# design.net
KiCad netlist of a schematic drawn in EasyEDA Pro
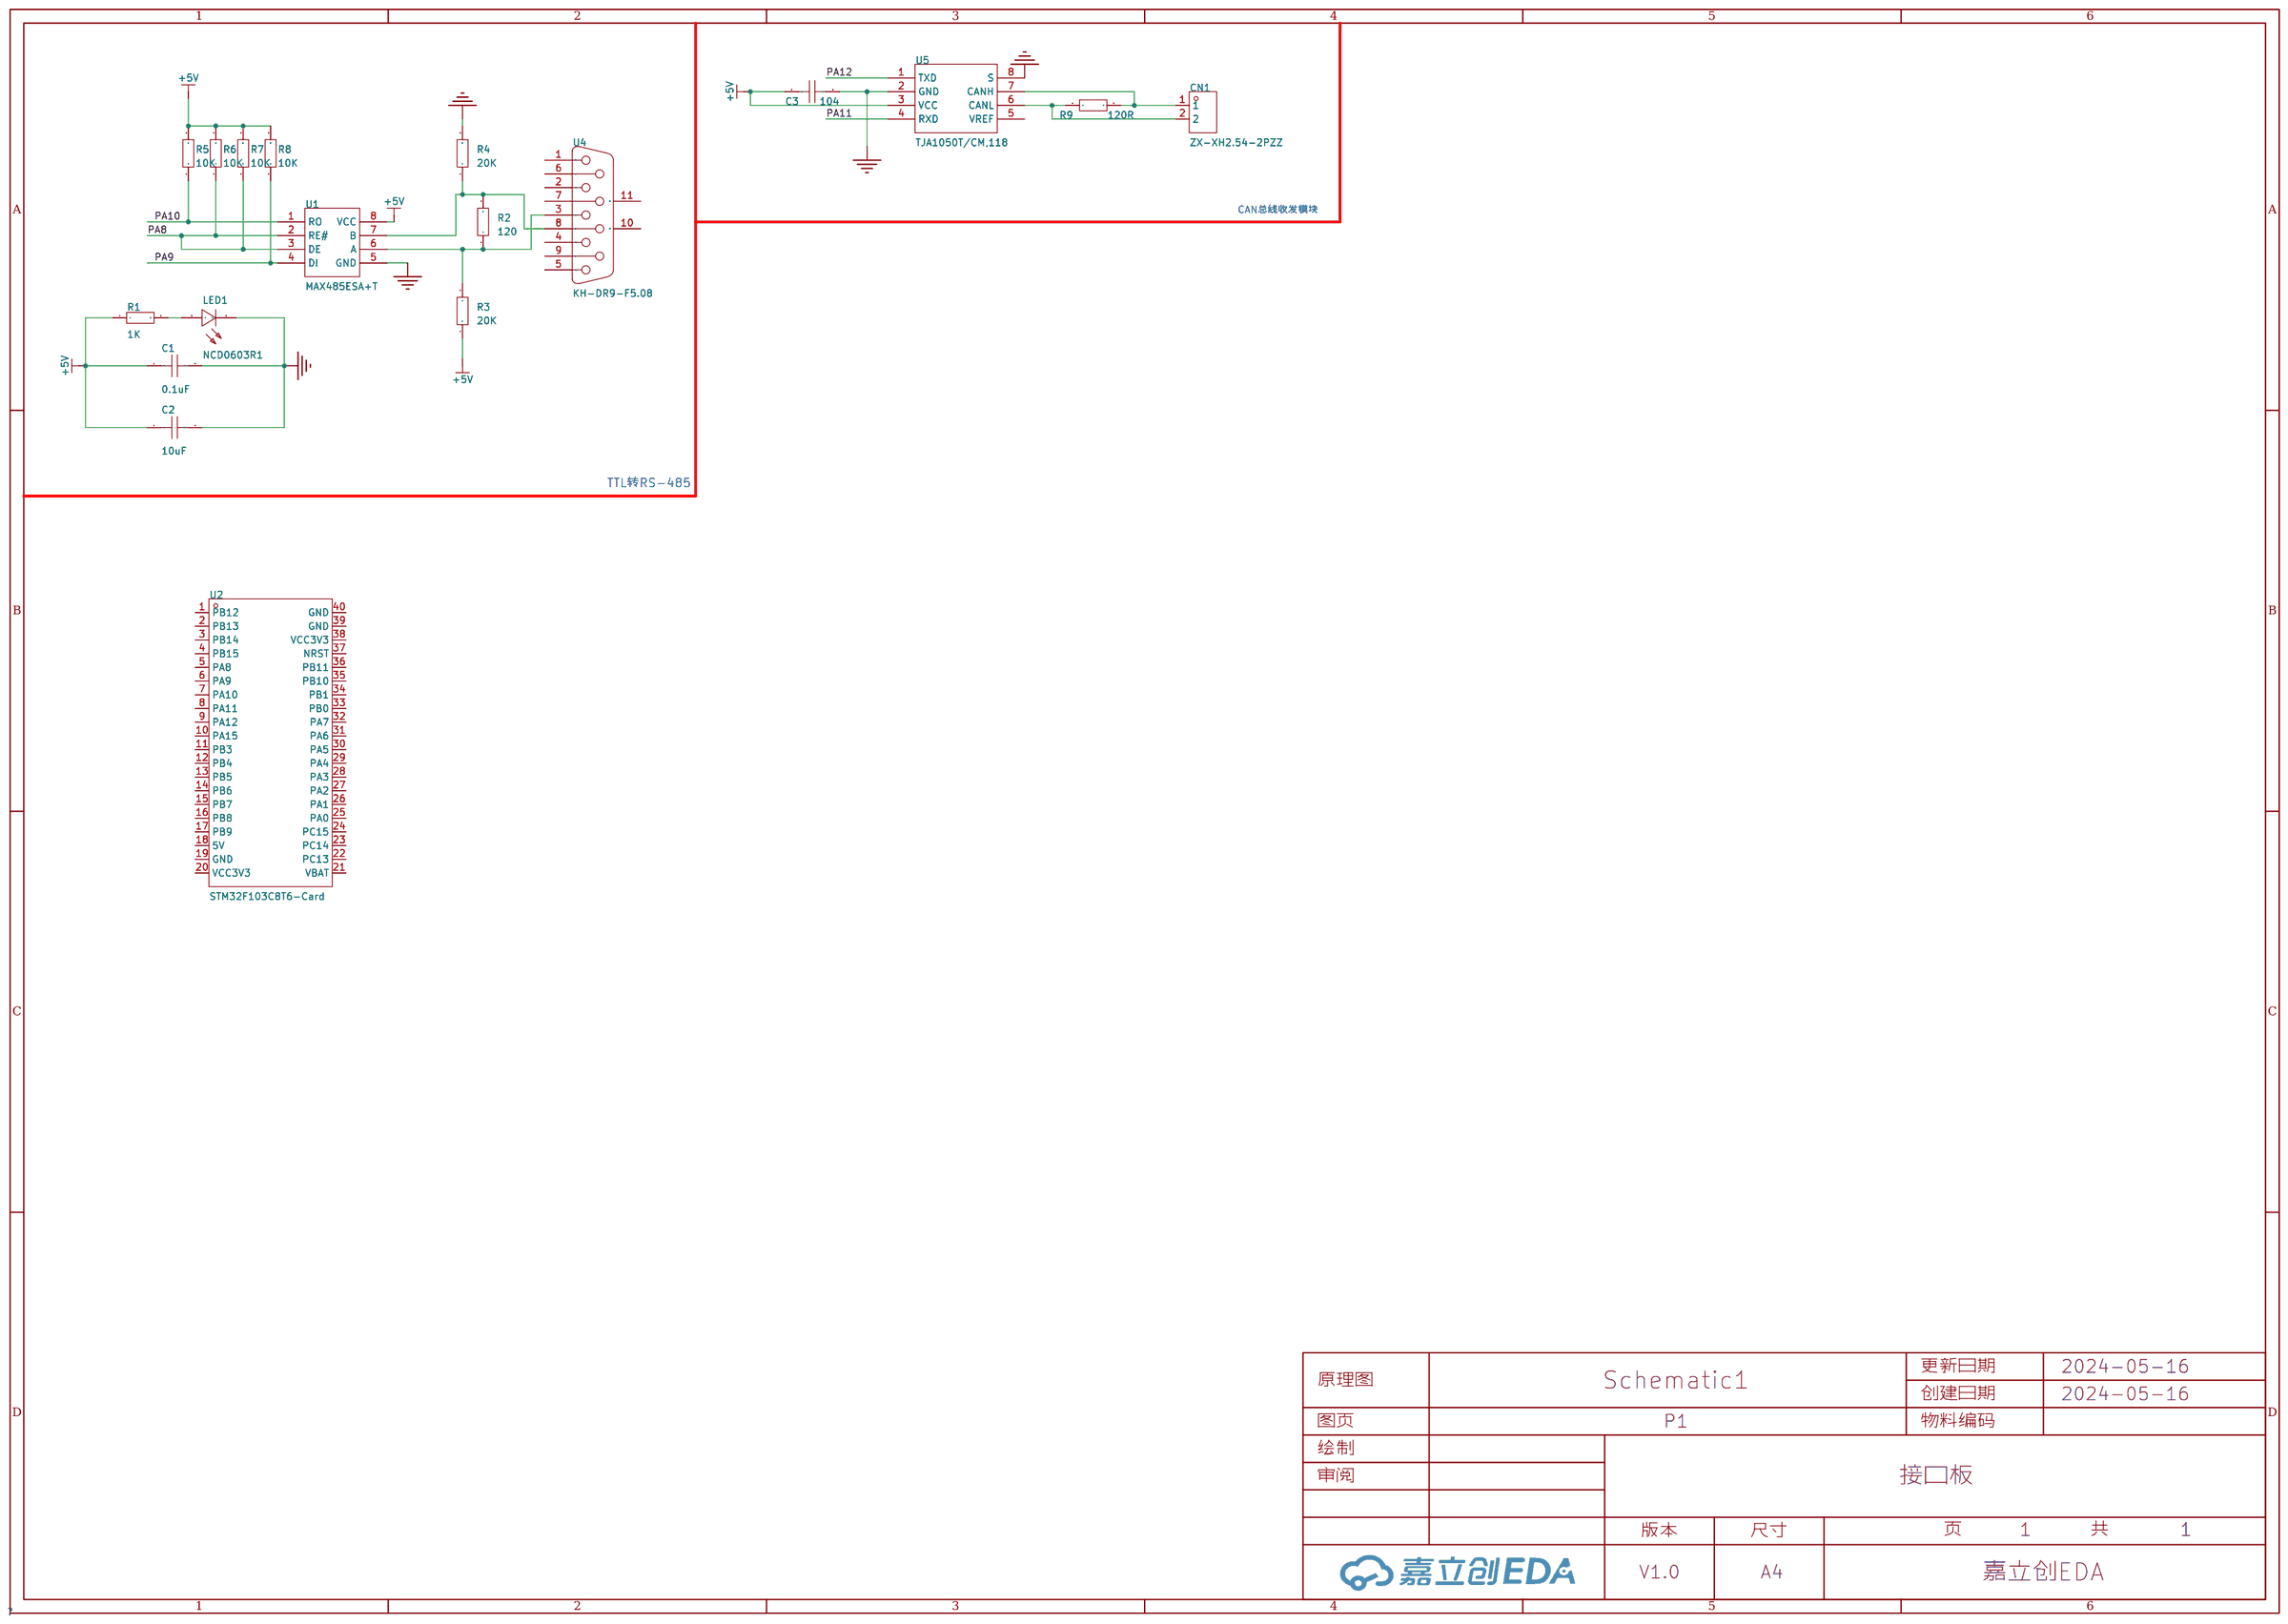
[diagram p0: schematic sheet]

(export (version "E")
  (design (tool "Eeschema 10.0.6"))
  (components
    (comp (ref "C1")
      (value "0.1uF")
      (footprint "easyedapro:C0603")
      (libsource (lib "easyedapro") (part "CapAcitance"))
    )
    (comp (ref "C2")
      (value "10uF")
      (footprint "easyedapro:C0603")
      (libsource (lib "easyedapro") (part "CapAcitance"))
    )
    (comp (ref "C3")
      (value "104")
      (footprint "easyedapro:C0603")
      (libsource (lib "easyedapro") (part "CapAcitance"))
    )
    (comp (ref "CN1")
      (value "ZX-XH2.54-2PZZ")
      (footprint "easyedapro:CONN-TH_2P-P2.50_HX25003-2A")
      (fields (field (name "Manufacturer") "Megastar(兆星)"))
      (libsource (lib "easyedapro") (part "ZX-XH2.54-2PZZ"))
    )
    (comp (ref "LED1")
      (value "NCD0603R1")
      (footprint "easyedapro:LED0603-RD_RED")
      (fields (field (name "Manufacturer") "国星光电"))
      (libsource (lib "easyedapro") (part "FC-DA1608HRK-620D"))
    )
    (comp (ref "R1") (value "1K") (footprint "easyedapro:R0603") (libsource (lib "easyedapro") (part "电阻")))
    (comp (ref "R2") (value "120") (footprint "easyedapro:R0603") (libsource (lib "easyedapro") (part "电阻")))
    (comp (ref "R3") (value "20K") (footprint "easyedapro:R0603") (libsource (lib "easyedapro") (part "电阻")))
    (comp (ref "R4") (value "20K") (footprint "easyedapro:R0603") (libsource (lib "easyedapro") (part "电阻")))
    (comp (ref "R5") (value "10K") (footprint "easyedapro:R0603") (libsource (lib "easyedapro") (part "电阻")))
    (comp (ref "R6") (value "10K") (footprint "easyedapro:R0603") (libsource (lib "easyedapro") (part "电阻")))
    (comp (ref "R7") (value "10K") (footprint "easyedapro:R0603") (libsource (lib "easyedapro") (part "电阻")))
    (comp (ref "R8") (value "10K") (footprint "easyedapro:R0603") (libsource (lib "easyedapro") (part "电阻")))
    (comp (ref "R9") (value "120R") (footprint "easyedapro:R0603") (libsource (lib "easyedapro") (part "电阻")))
    (comp (ref "U1")
      (value "MAX485ESA+T")
      (footprint "easyedapro:SOIC-8_L5.0-W4.0-P1.27-LS6.0-BL")
      (description "类型:收发器;数据速率:2.5Mbps;驱动器/接收器:1/1;")
      (fields (field (name "Manufacturer") "ADI(亚德诺)/MAXIM(美信)"))
      (libsource (lib "easyedapro") (part "MAX485ESA+T"))
    )
    (comp (ref "U2")
      (value "STM32F103C8T6-Card")
      (footprint "easyedapro:CONN-TH_L53.3-W22.9_STM32F103C8T6-CARD")
      (libsource (lib "easyedapro") (part "STM32F103C8T6-CARD"))
    )
    (comp (ref "U4")
      (value "KH-DR9-F5.08")
      (footprint "easyedapro:DB9-TH_KH-DR9-F5.08")
      (description "连接器类型:D-Sub;公母:母;总PIN位数:9P;")
      (fields (field (name "Manufacturer") "kinghelm(金航标)"))
      (libsource (lib "easyedapro") (part "KH-DR9-F5.08"))
    )
    (comp (ref "U5")
      (value "TJA1050T/CM,118")
      (footprint "easyedapro:SOIC-8_L5.0-W4.0-P1.27-LS6.0-BL")
      (description "类型:收发器;")
      (fields (field (name "Manufacturer") "NXP(恩智浦)"))
      (libsource (lib "easyedapro") (part "TJA1050T/CM,118"))
    )
  )
  (nets
    (net (code "1") (name "+5V") (class "Default")
      (node (ref "C1") (pin "1") (pinfunction "1_1") (pintype "input"))
      (node (ref "C2") (pin "1") (pinfunction "1_1") (pintype "input"))
      (node (ref "C3") (pin "1") (pinfunction "1_1") (pintype "input"))
      (node (ref "R1") (pin "1") (pinfunction "1_1") (pintype "input"))
      (node (ref "R3") (pin "1") (pinfunction "1_1") (pintype "input"))
      (node (ref "R5") (pin "2") (pinfunction "2_2") (pintype "input"))
      (node (ref "R6") (pin "2") (pinfunction "2_2") (pintype "input"))
      (node (ref "R7") (pin "2") (pinfunction "2_2") (pintype "input"))
      (node (ref "R8") (pin "2") (pinfunction "2_2") (pintype "input"))
      (node (ref "U1") (pin "8") (pinfunction "VCC_8") (pintype "unspecified"))
      (node (ref "U5") (pin "3") (pinfunction "VCC_3") (pintype "unspecified"))
    )
    (net (code "2") (name "/PA8") (class "Default")
      (node (ref "R6") (pin "1") (pinfunction "1_1") (pintype "input"))
      (node (ref "R7") (pin "1") (pinfunction "1_1") (pintype "input"))
      (node (ref "U1") (pin "2") (pinfunction "RE#_2") (pintype "unspecified"))
      (node (ref "U1") (pin "3") (pinfunction "DE_3") (pintype "unspecified"))
    )
    (net (code "3") (name "/PA9") (class "Default")
      (node (ref "R8") (pin "1") (pinfunction "1_1") (pintype "input"))
      (node (ref "U1") (pin "4") (pinfunction "DI_4") (pintype "unspecified"))
    )
    (net (code "4") (name "/PA10") (class "Default")
      (node (ref "R5") (pin "1") (pinfunction "1_1") (pintype "input"))
      (node (ref "U1") (pin "1") (pinfunction "RO_1") (pintype "unspecified"))
    )
    (net (code "5") (name "/PA11") (class "Default")
      (node (ref "U5") (pin "4") (pinfunction "RXD_4") (pintype "unspecified"))
    )
    (net (code "6") (name "/PA12") (class "Default")
      (node (ref "U5") (pin "1") (pinfunction "TXD_1") (pintype "unspecified"))
    )
    (net (code "7") (name "GND") (class "Default")
      (node (ref "C1") (pin "2") (pinfunction "2_2") (pintype "input"))
      (node (ref "C2") (pin "2") (pinfunction "2_2") (pintype "input"))
      (node (ref "C3") (pin "2") (pinfunction "2_2") (pintype "input"))
      (node (ref "LED1") (pin "1") (pinfunction "K_1") (pintype "input"))
      (node (ref "R4") (pin "2") (pinfunction "2_2") (pintype "input"))
      (node (ref "U1") (pin "5") (pinfunction "GND_5") (pintype "unspecified"))
      (node (ref "U5") (pin "2") (pinfunction "GND_2") (pintype "unspecified"))
      (node (ref "U5") (pin "8") (pinfunction "S_8") (pintype "unspecified"))
    )
    (net (code "8") (name "Net-(LED1-A)") (class "Default")
      (node (ref "LED1") (pin "2") (pinfunction "A_2") (pintype "input"))
      (node (ref "R1") (pin "2") (pinfunction "2_2") (pintype "input"))
    )
    (net (code "9") (name "Net-(U1-A)") (class "Default")
      (node (ref "R2") (pin "1") (pinfunction "1_1") (pintype "input"))
      (node (ref "R3") (pin "2") (pinfunction "2_2") (pintype "input"))
      (node (ref "U1") (pin "6") (pinfunction "A_6") (pintype "unspecified"))
      (node (ref "U4") (pin "3") (pinfunction "3_3") (pintype "input"))
    )
    (net (code "10") (name "Net-(U1-B)") (class "Default")
      (node (ref "R2") (pin "2") (pinfunction "2_2") (pintype "input"))
      (node (ref "R4") (pin "1") (pinfunction "1_1") (pintype "input"))
      (node (ref "U1") (pin "7") (pinfunction "B_7") (pintype "unspecified"))
      (node (ref "U4") (pin "8") (pinfunction "8_8") (pintype "input"))
    )
    (net (code "11") (name "Net-(U5-CANH)") (class "Default")
      (node (ref "CN1") (pin "1") (pinfunction "1_1") (pintype "unspecified"))
      (node (ref "R9") (pin "2") (pinfunction "2_2") (pintype "input"))
      (node (ref "U5") (pin "7") (pinfunction "CANH_7") (pintype "unspecified"))
    )
    (net (code "12") (name "Net-(U5-CANL)") (class "Default")
      (node (ref "CN1") (pin "2") (pinfunction "2_2") (pintype "unspecified"))
      (node (ref "R9") (pin "1") (pinfunction "1_1") (pintype "input"))
      (node (ref "U5") (pin "6") (pinfunction "CANL_6") (pintype "unspecified"))
    )
    (net (code "13") (name "unconnected-(U2-5V-Pad18)") (class "Default")
      (node (ref "U2") (pin "18") (pinfunction "5V_18") (pintype "unspecified"))
    )
    (net (code "14") (name "unconnected-(U2-GND-Pad19)") (class "Default")
      (node (ref "U2") (pin "19") (pinfunction "GND_19") (pintype "unspecified"))
    )
    (net (code "15") (name "unconnected-(U2-GND-Pad39)") (class "Default")
      (node (ref "U2") (pin "39") (pinfunction "GND_39") (pintype "unspecified"))
    )
    (net (code "16") (name "unconnected-(U2-GND-Pad40)") (class "Default")
      (node (ref "U2") (pin "40") (pinfunction "GND_40") (pintype "unspecified"))
    )
    (net (code "17") (name "unconnected-(U2-NRST-Pad37)") (class "Default")
      (node (ref "U2") (pin "37") (pinfunction "NRST_37") (pintype "unspecified"))
    )
    (net (code "18") (name "unconnected-(U2-PA0-Pad25)") (class "Default")
      (node (ref "U2") (pin "25") (pinfunction "PA0_25") (pintype "unspecified"))
    )
    (net (code "19") (name "unconnected-(U2-PA1-Pad26)") (class "Default")
      (node (ref "U2") (pin "26") (pinfunction "PA1_26") (pintype "unspecified"))
    )
    (net (code "20") (name "unconnected-(U2-PA2-Pad27)") (class "Default")
      (node (ref "U2") (pin "27") (pinfunction "PA2_27") (pintype "unspecified"))
    )
    (net (code "21") (name "unconnected-(U2-PA3-Pad28)") (class "Default")
      (node (ref "U2") (pin "28") (pinfunction "PA3_28") (pintype "unspecified"))
    )
    (net (code "22") (name "unconnected-(U2-PA4-Pad29)") (class "Default")
      (node (ref "U2") (pin "29") (pinfunction "PA4_29") (pintype "unspecified"))
    )
    (net (code "23") (name "unconnected-(U2-PA5-Pad30)") (class "Default")
      (node (ref "U2") (pin "30") (pinfunction "PA5_30") (pintype "unspecified"))
    )
    (net (code "24") (name "unconnected-(U2-PA6-Pad31)") (class "Default")
      (node (ref "U2") (pin "31") (pinfunction "PA6_31") (pintype "unspecified"))
    )
    (net (code "25") (name "unconnected-(U2-PA7-Pad32)") (class "Default")
      (node (ref "U2") (pin "32") (pinfunction "PA7_32") (pintype "unspecified"))
    )
    (net (code "26") (name "unconnected-(U2-PA8-Pad5)") (class "Default")
      (node (ref "U2") (pin "5") (pinfunction "PA8_5") (pintype "unspecified"))
    )
    (net (code "27") (name "unconnected-(U2-PA9-Pad6)") (class "Default")
      (node (ref "U2") (pin "6") (pinfunction "PA9_6") (pintype "unspecified"))
    )
    (net (code "28") (name "unconnected-(U2-PA10-Pad7)") (class "Default")
      (node (ref "U2") (pin "7") (pinfunction "PA10_7") (pintype "unspecified"))
    )
    (net (code "29") (name "unconnected-(U2-PA11-Pad8)") (class "Default")
      (node (ref "U2") (pin "8") (pinfunction "PA11_8") (pintype "unspecified"))
    )
    (net (code "30") (name "unconnected-(U2-PA12-Pad9)") (class "Default")
      (node (ref "U2") (pin "9") (pinfunction "PA12_9") (pintype "unspecified"))
    )
    (net (code "31") (name "unconnected-(U2-PA15-Pad10)") (class "Default")
      (node (ref "U2") (pin "10") (pinfunction "PA15_10") (pintype "unspecified"))
    )
    (net (code "32") (name "unconnected-(U2-PB0-Pad33)") (class "Default")
      (node (ref "U2") (pin "33") (pinfunction "PB0_33") (pintype "unspecified"))
    )
    (net (code "33") (name "unconnected-(U2-PB1-Pad34)") (class "Default")
      (node (ref "U2") (pin "34") (pinfunction "PB1_34") (pintype "unspecified"))
    )
    (net (code "34") (name "unconnected-(U2-PB3-Pad11)") (class "Default")
      (node (ref "U2") (pin "11") (pinfunction "PB3_11") (pintype "unspecified"))
    )
    (net (code "35") (name "unconnected-(U2-PB4-Pad12)") (class "Default")
      (node (ref "U2") (pin "12") (pinfunction "PB4_12") (pintype "unspecified"))
    )
    (net (code "36") (name "unconnected-(U2-PB5-Pad13)") (class "Default")
      (node (ref "U2") (pin "13") (pinfunction "PB5_13") (pintype "unspecified"))
    )
    (net (code "37") (name "unconnected-(U2-PB6-Pad14)") (class "Default")
      (node (ref "U2") (pin "14") (pinfunction "PB6_14") (pintype "unspecified"))
    )
    (net (code "38") (name "unconnected-(U2-PB7-Pad15)") (class "Default")
      (node (ref "U2") (pin "15") (pinfunction "PB7_15") (pintype "unspecified"))
    )
    (net (code "39") (name "unconnected-(U2-PB8-Pad16)") (class "Default")
      (node (ref "U2") (pin "16") (pinfunction "PB8_16") (pintype "unspecified"))
    )
    (net (code "40") (name "unconnected-(U2-PB9-Pad17)") (class "Default")
      (node (ref "U2") (pin "17") (pinfunction "PB9_17") (pintype "unspecified"))
    )
    (net (code "41") (name "unconnected-(U2-PB10-Pad35)") (class "Default")
      (node (ref "U2") (pin "35") (pinfunction "PB10_35") (pintype "unspecified"))
    )
    (net (code "42") (name "unconnected-(U2-PB11-Pad36)") (class "Default")
      (node (ref "U2") (pin "36") (pinfunction "PB11_36") (pintype "unspecified"))
    )
    (net (code "43") (name "unconnected-(U2-PB12-Pad1)") (class "Default")
      (node (ref "U2") (pin "1") (pinfunction "PB12_1") (pintype "unspecified"))
    )
    (net (code "44") (name "unconnected-(U2-PB13-Pad2)") (class "Default")
      (node (ref "U2") (pin "2") (pinfunction "PB13_2") (pintype "unspecified"))
    )
    (net (code "45") (name "unconnected-(U2-PB14-Pad3)") (class "Default")
      (node (ref "U2") (pin "3") (pinfunction "PB14_3") (pintype "unspecified"))
    )
    (net (code "46") (name "unconnected-(U2-PB15-Pad4)") (class "Default")
      (node (ref "U2") (pin "4") (pinfunction "PB15_4") (pintype "unspecified"))
    )
    (net (code "47") (name "unconnected-(U2-PC13-Pad22)") (class "Default")
      (node (ref "U2") (pin "22") (pinfunction "PC13_22") (pintype "unspecified"))
    )
    (net (code "48") (name "unconnected-(U2-PC14-Pad23)") (class "Default")
      (node (ref "U2") (pin "23") (pinfunction "PC14_23") (pintype "unspecified"))
    )
    (net (code "49") (name "unconnected-(U2-PC15-Pad24)") (class "Default")
      (node (ref "U2") (pin "24") (pinfunction "PC15_24") (pintype "unspecified"))
    )
    (net (code "50") (name "unconnected-(U2-VBAT-Pad21)") (class "Default")
      (node (ref "U2") (pin "21") (pinfunction "VBAT_21") (pintype "unspecified"))
    )
    (net (code "51") (name "unconnected-(U2-VCC3V3-Pad20)") (class "Default")
      (node (ref "U2") (pin "20") (pinfunction "VCC3V3_20") (pintype "unspecified"))
    )
    (net (code "52") (name "unconnected-(U2-VCC3V3-Pad38)") (class "Default")
      (node (ref "U2") (pin "38") (pinfunction "VCC3V3_38") (pintype "unspecified"))
    )
    (net (code "53") (name "unconnected-(U4-MH1-Pad10)") (class "Default")
      (node (ref "U4") (pin "10") (pinfunction "MH1_10") (pintype "input"))
    )
    (net (code "54") (name "unconnected-(U4-MH2-Pad11)") (class "Default")
      (node (ref "U4") (pin "11") (pinfunction "MH2_11") (pintype "input"))
    )
    (net (code "55") (name "unconnected-(U4-Pad1)") (class "Default")
      (node (ref "U4") (pin "1") (pinfunction "1_1") (pintype "input"))
    )
    (net (code "56") (name "unconnected-(U4-Pad2)") (class "Default")
      (node (ref "U4") (pin "2") (pinfunction "2_2") (pintype "input"))
    )
    (net (code "57") (name "unconnected-(U4-Pad4)") (class "Default")
      (node (ref "U4") (pin "4") (pinfunction "4_4") (pintype "input"))
    )
    (net (code "58") (name "unconnected-(U4-Pad5)") (class "Default")
      (node (ref "U4") (pin "5") (pinfunction "5_5") (pintype "input"))
    )
    (net (code "59") (name "unconnected-(U4-Pad6)") (class "Default")
      (node (ref "U4") (pin "6") (pinfunction "6_6") (pintype "input"))
    )
    (net (code "60") (name "unconnected-(U4-Pad7)") (class "Default")
      (node (ref "U4") (pin "7") (pinfunction "7_7") (pintype "input"))
    )
    (net (code "61") (name "unconnected-(U4-Pad9)") (class "Default")
      (node (ref "U4") (pin "9") (pinfunction "9_9") (pintype "input"))
    )
    (net (code "62") (name "unconnected-(U5-VREF-Pad5)") (class "Default")
      (node (ref "U5") (pin "5") (pinfunction "VREF_5") (pintype "unspecified"))
    )
  )
)
